# MainBoard_V100_CHARGER.net
KiCad netlist of a schematic drawn in Altium Designer
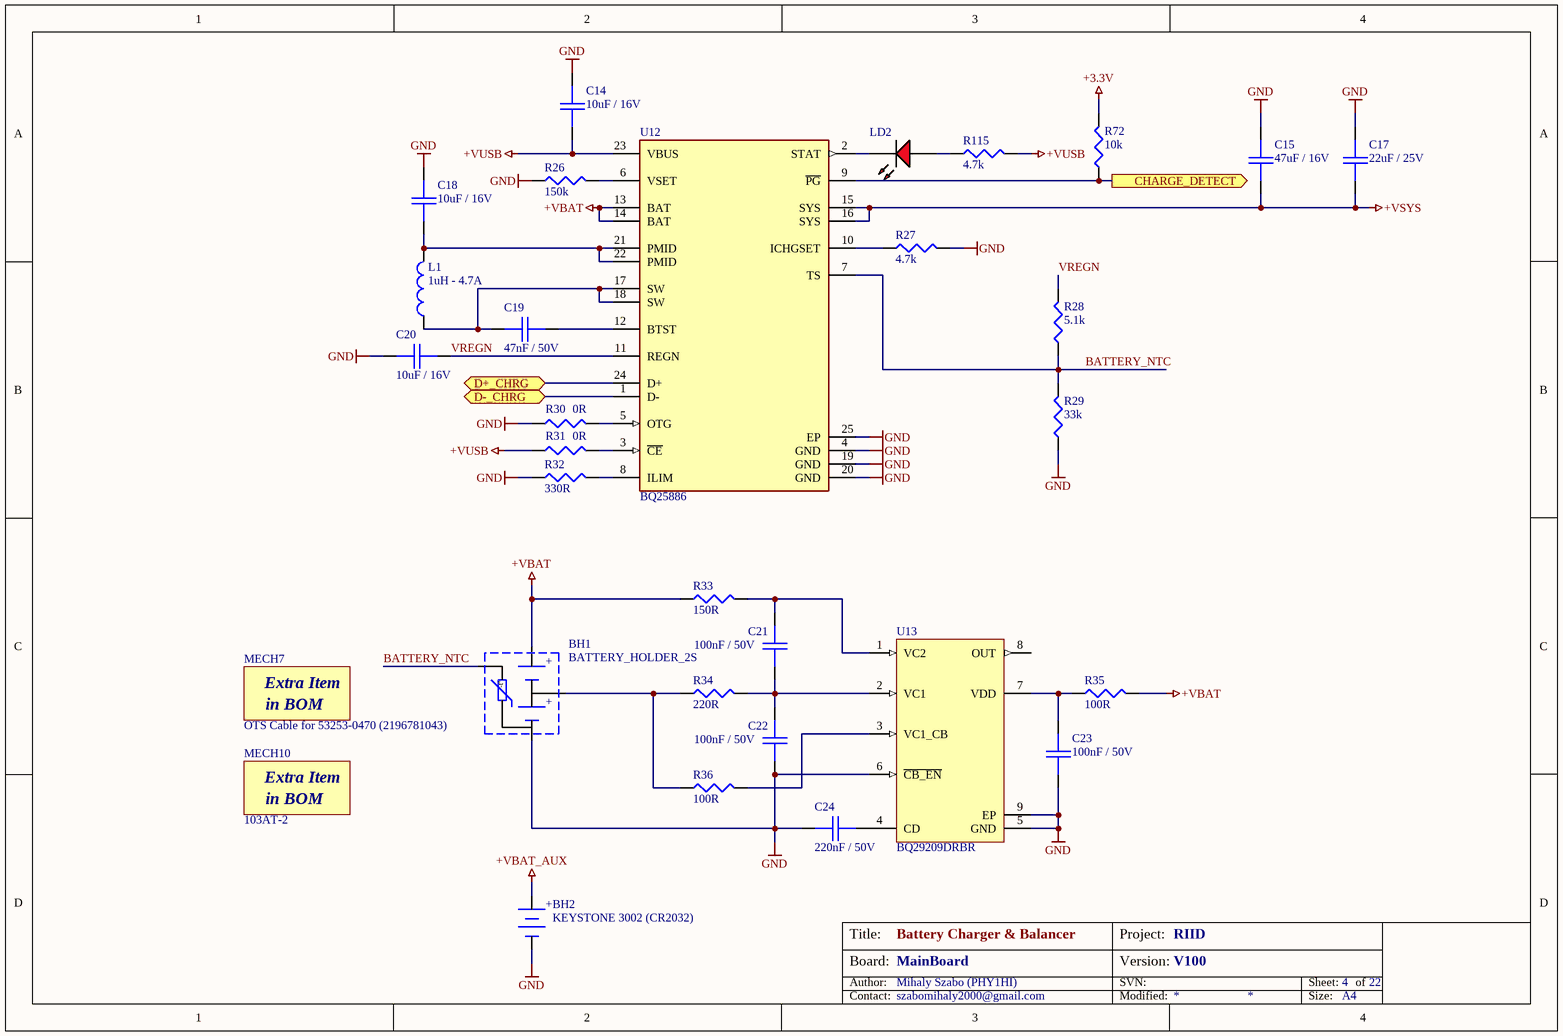
[diagram p0: MainBoard_V100_CHARGER.SchDoc]

(export (version "E")
  (design (tool "Eeschema 10.0.6"))
  (components
    (comp (ref "BH1")
      (value "BATTERY_HOLDER_2S")
      (footprint "MOLEX-53253-0470")
      (description "2S Battery with NTC thermistor")
      (libsource (lib "ALTIUM_DB_LIB") (part "BATTERY_HOLDER_2S"))
    )
    (comp (ref "BH2")
      (value "KEYSTONE 3002 (CR2032)")
      (footprint "BATTERY_HOLDER_KEYSTONE_3002")
      (description "Battery Holder, CR2032")
      (fields (field (name "PART NUMBER") "BATTERY_HOLDER_CR2032"))
      (libsource (lib "ALTIUM_DB_LIB") (part "BATTERY_HOLDER"))
    )
    (comp (ref "C14")
      (value "10uF / 16V")
      (footprint "0805_C")
      (description "10uF 16V X5R")
      (fields (field (name "PART NUMBER") "SMD0805-10uF-16V"))
      (libsource (lib "ALTIUM_DB_LIB") (part "CAP_NONPOL"))
    )
    (comp (ref "C15")
      (value "47uF / 16V")
      (footprint "1210_C")
      (description "47uF 16V X5R")
      (fields (field (name "PART NUMBER") "SMD1210-47uF-16V"))
      (libsource (lib "ALTIUM_DB_LIB") (part "CAP_NONPOL"))
    )
    (comp (ref "C17")
      (value "22uF / 25V")
      (footprint "1210_C")
      (description "22uF 25V X5R")
      (fields (field (name "PART NUMBER") "SMD1210-22uF-25V"))
      (libsource (lib "ALTIUM_DB_LIB") (part "CAP_NONPOL"))
    )
    (comp (ref "C18")
      (value "10uF / 16V")
      (footprint "0805_C")
      (description "10uF 16V X5R")
      (fields (field (name "PART NUMBER") "SMD0805-10uF-16V"))
      (libsource (lib "ALTIUM_DB_LIB") (part "CAP_NONPOL"))
    )
    (comp (ref "C19")
      (value "47nF / 50V")
      (footprint "0805_C")
      (description "47nF 50V X7R")
      (fields (field (name "PART NUMBER") "SMD0805-47nF-50V"))
      (libsource (lib "ALTIUM_DB_LIB") (part "CAP_NONPOL"))
    )
    (comp (ref "C20")
      (value "10uF / 16V")
      (footprint "0805_C")
      (description "10uF 16V X5R")
      (fields (field (name "PART NUMBER") "SMD0805-10uF-16V"))
      (libsource (lib "ALTIUM_DB_LIB") (part "CAP_NONPOL"))
    )
    (comp (ref "C21")
      (value "100nF / 50V")
      (footprint "0805_C")
      (description "100nF 50V X7R")
      (fields (field (name "PART NUMBER") "SMD0805-100nF-50V"))
      (libsource (lib "ALTIUM_DB_LIB") (part "CAP_NONPOL"))
    )
    (comp (ref "C22")
      (value "100nF / 50V")
      (footprint "0805_C")
      (description "100nF 50V X7R")
      (fields (field (name "PART NUMBER") "SMD0805-100nF-50V"))
      (libsource (lib "ALTIUM_DB_LIB") (part "CAP_NONPOL"))
    )
    (comp (ref "C23")
      (value "100nF / 50V")
      (footprint "0805_C")
      (description "100nF 50V X7R")
      (fields (field (name "PART NUMBER") "SMD0805-100nF-50V"))
      (libsource (lib "ALTIUM_DB_LIB") (part "CAP_NONPOL"))
    )
    (comp (ref "C24")
      (value "220nF / 50V")
      (footprint "0805_C")
      (description "220nF 50V Y5V")
      (fields (field (name "PART NUMBER") "SMD0805-220nF-50V"))
      (libsource (lib "ALTIUM_DB_LIB") (part "CAP_NONPOL"))
    )
    (comp (ref "L1")
      (value "1uH - 4.7A")
      (footprint "2520_IND")
      (description "1uH  / 20% 4.7A")
      (fields (field (name "PART NUMBER") "SMD-2520-1uH-20%"))
      (libsource (lib "ALTIUM_DB_LIB") (part "INDUCTOR"))
    )
    (comp (ref "LD2")
      (value "HSMS-C110 (RED)")
      (footprint "LED_SMD_90DEG_RED")
      (description "LED, Red, SMD, 20 mA, 2.1 V, 626 nm")
      (fields (field (name "PART NUMBER") "HSMS-C110"))
      (libsource (lib "ALTIUM_DB_LIB") (part "LED_GENERAL_RED"))
    )
    (comp (ref "MECH7")
      (value "OTS Cable for 53253-0470 (2196781043)")
      (fields (field (name "PART NUMBER") "2196781043"))
      (libsource (lib "ALTIUM_DB_LIB") (part "Extra Part"))
    )
    (comp (ref "MECH10")
      (value "103AT-2")
      (description "NTC (Negative Temperature Coefficient) Thermistors 10kohm 1%")
      (libsource (lib "ALTIUM_DB_LIB") (part "Extra Part"))
    )
    (comp (ref "R26")
      (value "150k")
      (footprint "0805")
      (description "150k 0805 0.125W 1%")
      (fields (field (name "PART NUMBER") "SMD-0805-150k-1%"))
      (libsource (lib "ALTIUM_DB_LIB") (part "RESISTOR"))
    )
    (comp (ref "R27")
      (value "4.7k")
      (footprint "0805")
      (description "4.7k 0805 0.125W 5%")
      (fields (field (name "PART NUMBER") "SMD0805-4.7k 5%"))
      (libsource (lib "ALTIUM_DB_LIB") (part "RESISTOR"))
    )
    (comp (ref "R28")
      (value "5.1k")
      (footprint "0805")
      (description "5.1k 0805 0.125W 5%")
      (fields (field (name "PART NUMBER") "SMD0805-5.1k 5%"))
      (libsource (lib "ALTIUM_DB_LIB") (part "RESISTOR"))
    )
    (comp (ref "R29")
      (value "33k")
      (footprint "0805")
      (description "33k 0805 0.125W 5%")
      (fields (field (name "PART NUMBER") "SMD0805-33k 5%"))
      (libsource (lib "ALTIUM_DB_LIB") (part "RESISTOR"))
    )
    (comp (ref "R30")
      (value "0R")
      (footprint "0805")
      (description "0R 0805 0.125W 5%")
      (fields (field (name "PART NUMBER") "0 R 5%"))
      (libsource (lib "ALTIUM_DB_LIB") (part "RESISTOR"))
    )
    (comp (ref "R31")
      (value "0R")
      (footprint "0805")
      (description "0R 0805 0.125W 5%")
      (fields (field (name "PART NUMBER") "0 R 5%"))
      (libsource (lib "ALTIUM_DB_LIB") (part "RESISTOR"))
    )
    (comp (ref "R32")
      (value "330R")
      (footprint "0805")
      (description "330R 0805 0.125W 5%")
      (fields (field (name "PART NUMBER") "SMD0805-330R 5%"))
      (libsource (lib "ALTIUM_DB_LIB") (part "RESISTOR"))
    )
    (comp (ref "R33")
      (value "150R")
      (footprint "0805")
      (description "150R 0805 0.125W 5%")
      (fields (field (name "PART NUMBER") "SMD0805-150R 5%"))
      (libsource (lib "ALTIUM_DB_LIB") (part "RESISTOR"))
    )
    (comp (ref "R34")
      (value "220R")
      (footprint "0805")
      (description "220R 0805 0.125W 5%")
      (fields (field (name "PART NUMBER") "SMD0805-220R 5%"))
      (libsource (lib "ALTIUM_DB_LIB") (part "RESISTOR"))
    )
    (comp (ref "R35")
      (value "100R")
      (footprint "0805")
      (description "100R 0805 0.125W 5%")
      (fields (field (name "PART NUMBER") "SMD0805-100R 5%"))
      (libsource (lib "ALTIUM_DB_LIB") (part "RESISTOR"))
    )
    (comp (ref "R36")
      (value "100R")
      (footprint "0805")
      (description "100R 0805 0.125W 5%")
      (fields (field (name "PART NUMBER") "SMD0805-100R 5%"))
      (libsource (lib "ALTIUM_DB_LIB") (part "RESISTOR"))
    )
    (comp (ref "R72")
      (value "10k")
      (footprint "0805")
      (description "10k 0805 0.125W 1%")
      (fields (field (name "PART NUMBER") "SMD0805-10k 1%"))
      (libsource (lib "ALTIUM_DB_LIB") (part "RESISTOR"))
    )
    (comp (ref "R115")
      (value "4.7k")
      (footprint "0805")
      (description "4.7k 0805 0.125W 5%")
      (fields (field (name "PART NUMBER") "SMD0805-4.7k 5%"))
      (libsource (lib "ALTIUM_DB_LIB") (part "RESISTOR"))
    )
    (comp (ref "U12")
      (value "BQ25886")
      (footprint "VQFN-24")
      (libsource (lib "ALTIUM_DB_LIB") (part "BQ25886RGER"))
    )
    (comp (ref "U13")
      (value "BQ29209DRBR")
      (footprint "VSON-8")
      (fields (field (name "MANUFACTURER") "Texas Instruments"))
      (libsource (lib "ALTIUM_DB_LIB") (part "BQ29209DRBR"))
    )
  )
  (nets
    (net (code "1") (name "+3.3V") (class "Default") (node (ref "R72") (pin "2") (pintype "passive")))
    (net (code "2") (name "+VBAT") (class "Default")
      (node (ref "BH1") (pin "1") (pinfunction "1_1") (pintype "passive"))
      (node (ref "R33") (pin "1") (pintype "passive"))
      (node (ref "R35") (pin "1") (pintype "passive"))
      (node (ref "U12") (pin "13") (pinfunction "BAT_13") (pintype "power_in"))
      (node (ref "U12") (pin "14") (pinfunction "BAT_14") (pintype "power_in"))
    )
    (net (code "3") (name "+VBAT_AUX") (class "Default")
      (node (ref "BH2") (pin "1") (pinfunction "1_1") (pintype "passive"))
    )
    (net (code "4") (name "+VSYS") (class "Default")
      (node (ref "C15") (pin "2") (pintype "passive"))
      (node (ref "C17") (pin "2") (pintype "passive"))
      (node (ref "U12") (pin "15") (pinfunction "SYS_15") (pintype "power_in"))
      (node (ref "U12") (pin "16") (pinfunction "SYS_16") (pintype "power_in"))
    )
    (net (code "5") (name "+VUSB") (class "Default")
      (node (ref "C14") (pin "2") (pintype "passive"))
      (node (ref "R115") (pin "2") (pintype "passive"))
      (node (ref "R31") (pin "1") (pintype "passive"))
      (node (ref "U12") (pin "23") (pinfunction "VBUS_23") (pintype "power_in"))
    )
    (net (code "6") (name "/BATTERY_NTC") (class "Default")
      (node (ref "BH1") (pin "4") (pintype "passive"))
      (node (ref "R28") (pin "1") (pintype "passive"))
      (node (ref "R29") (pin "2") (pintype "passive"))
      (node (ref "U12") (pin "7") (pinfunction "TS_7") (pintype "passive"))
    )
    (net (code "7") (name "/CHARGE_DETECT") (class "Default")
      (node (ref "R72") (pin "1") (pintype "passive"))
      (node (ref "U12") (pin "9") (pinfunction "~{PG}_9") (pintype "open_collector"))
    )
    (net (code "8") (name "/D+_CHRG") (class "Default")
      (node (ref "U12") (pin "24") (pinfunction "D+_24") (pintype "passive"))
    )
    (net (code "9") (name "/D-_CHRG") (class "Default")
      (node (ref "U12") (pin "1") (pinfunction "D-_1") (pintype "passive"))
    )
    (net (code "10") (name "/VREGN") (class "Default")
      (node (ref "C20") (pin "2") (pintype "passive"))
      (node (ref "R28") (pin "2") (pintype "passive"))
      (node (ref "U12") (pin "11") (pinfunction "REGN_11") (pintype "power_in"))
    )
    (net (code "11") (name "GND") (class "Default")
      (node (ref "BH1") (pin "3") (pinfunction "3_3") (pintype "passive"))
      (node (ref "BH2") (pin "2") (pinfunction "2_2") (pintype "passive"))
      (node (ref "C14") (pin "1") (pintype "passive"))
      (node (ref "C15") (pin "1") (pintype "passive"))
      (node (ref "C17") (pin "1") (pintype "passive"))
      (node (ref "C18") (pin "1") (pintype "passive"))
      (node (ref "C20") (pin "1") (pintype "passive"))
      (node (ref "C22") (pin "2") (pintype "passive"))
      (node (ref "C23") (pin "1") (pintype "passive"))
      (node (ref "C24") (pin "1") (pintype "passive"))
      (node (ref "R26") (pin "1") (pintype "passive"))
      (node (ref "R27") (pin "2") (pintype "passive"))
      (node (ref "R29") (pin "1") (pintype "passive"))
      (node (ref "R30") (pin "1") (pintype "passive"))
      (node (ref "R32") (pin "1") (pintype "passive"))
      (node (ref "U12") (pin "19") (pinfunction "GND_19") (pintype "power_in"))
      (node (ref "U12") (pin "20") (pinfunction "GND_20") (pintype "power_in"))
      (node (ref "U12") (pin "25") (pinfunction "EP_25") (pintype "power_in"))
      (node (ref "U12") (pin "4") (pinfunction "GND_4") (pintype "power_in"))
      (node (ref "U13") (pin "5") (pinfunction "GND_5") (pintype "power_in"))
      (node (ref "U13") (pin "6") (pinfunction "~{CB_EN}_6") (pintype "input"))
      (node (ref "U13") (pin "9") (pinfunction "EP_9") (pintype "passive"))
    )
    (net (code "12") (name "Net-(BH1-Pad2)") (class "Default")
      (node (ref "BH1") (pin "2") (pinfunction "2_2") (pintype "passive"))
      (node (ref "R34") (pin "1") (pintype "passive"))
      (node (ref "R36") (pin "1") (pintype "passive"))
    )
    (net (code "13") (name "Net-(C18-Pad2)") (class "Default")
      (node (ref "C18") (pin "2") (pintype "passive"))
      (node (ref "L1") (pin "2") (pinfunction "2_2") (pintype "passive"))
      (node (ref "U12") (pin "21") (pinfunction "PMID_21") (pintype "power_in"))
      (node (ref "U12") (pin "22") (pinfunction "PMID_22") (pintype "power_in"))
    )
    (net (code "14") (name "Net-(C19-Pad1)") (class "Default")
      (node (ref "C19") (pin "1") (pintype "passive"))
      (node (ref "L1") (pin "1") (pinfunction "1_1") (pintype "passive"))
      (node (ref "U12") (pin "17") (pinfunction "SW_17") (pintype "power_in"))
      (node (ref "U12") (pin "18") (pinfunction "SW_18") (pintype "power_in"))
    )
    (net (code "15") (name "Net-(LD2-PadA)") (class "Default")
      (node (ref "LD2") (pin "A") (pinfunction "A_A") (pintype "passive"))
      (node (ref "R115") (pin "1") (pintype "passive"))
    )
    (net (code "16") (name "Net-(U12-BTST)") (class "Default")
      (node (ref "C19") (pin "2") (pintype "passive"))
      (node (ref "U12") (pin "12") (pinfunction "BTST_12") (pintype "power_in"))
    )
    (net (code "17") (name "Net-(U12-ICHGSET)") (class "Default")
      (node (ref "R27") (pin "1") (pintype "passive"))
      (node (ref "U12") (pin "10") (pinfunction "ICHGSET_10") (pintype "passive"))
    )
    (net (code "18") (name "Net-(U12-ILIM)") (class "Default")
      (node (ref "R32") (pin "2") (pintype "passive"))
      (node (ref "U12") (pin "8") (pinfunction "ILIM_8") (pintype "passive"))
    )
    (net (code "19") (name "Net-(U12-OTG)") (class "Default")
      (node (ref "R30") (pin "2") (pintype "passive"))
      (node (ref "U12") (pin "5") (pinfunction "OTG_5") (pintype "input"))
    )
    (net (code "20") (name "Net-(U12-STAT)") (class "Default")
      (node (ref "LD2") (pin "K") (pinfunction "K_K") (pintype "passive"))
      (node (ref "U12") (pin "2") (pinfunction "STAT_2") (pintype "output"))
    )
    (net (code "21") (name "Net-(U12-VSET)") (class "Default")
      (node (ref "R26") (pin "2") (pintype "passive"))
      (node (ref "U12") (pin "6") (pinfunction "VSET_6") (pintype "passive"))
    )
    (net (code "22") (name "Net-(U12-~{CE})") (class "Default")
      (node (ref "R31") (pin "2") (pintype "passive"))
      (node (ref "U12") (pin "3") (pinfunction "~{CE}_3") (pintype "input"))
    )
    (net (code "23") (name "Net-(U13-CD)") (class "Default")
      (node (ref "C24") (pin "2") (pintype "passive"))
      (node (ref "U13") (pin "4") (pinfunction "CD_4") (pintype "passive"))
    )
    (net (code "24") (name "Net-(U13-VC1)") (class "Default")
      (node (ref "C21") (pin "2") (pintype "passive"))
      (node (ref "C22") (pin "1") (pintype "passive"))
      (node (ref "R34") (pin "2") (pintype "passive"))
      (node (ref "U13") (pin "2") (pinfunction "VC1_2") (pintype "input"))
    )
    (net (code "25") (name "Net-(U13-VC1_CB)") (class "Default")
      (node (ref "R36") (pin "2") (pintype "passive"))
      (node (ref "U13") (pin "3") (pinfunction "VC1_CB_3") (pintype "input"))
    )
    (net (code "26") (name "Net-(U13-VC2)") (class "Default")
      (node (ref "C21") (pin "1") (pintype "passive"))
      (node (ref "R33") (pin "2") (pintype "passive"))
      (node (ref "U13") (pin "1") (pinfunction "VC2_1") (pintype "input"))
    )
    (net (code "27") (name "Net-(U13-VDD)") (class "Default")
      (node (ref "C23") (pin "2") (pintype "passive"))
      (node (ref "R35") (pin "2") (pintype "passive"))
      (node (ref "U13") (pin "7") (pinfunction "VDD_7") (pintype "power_in"))
    )
    (net (code "28") (name "unconnected-(U13-OUT-Pad8)") (class "Default")
      (node (ref "U13") (pin "8") (pinfunction "OUT_8") (pintype "output"))
    )
  )
)
